# Microcontroleur.net
KiCad netlist of a schematic drawn in Altium Designer
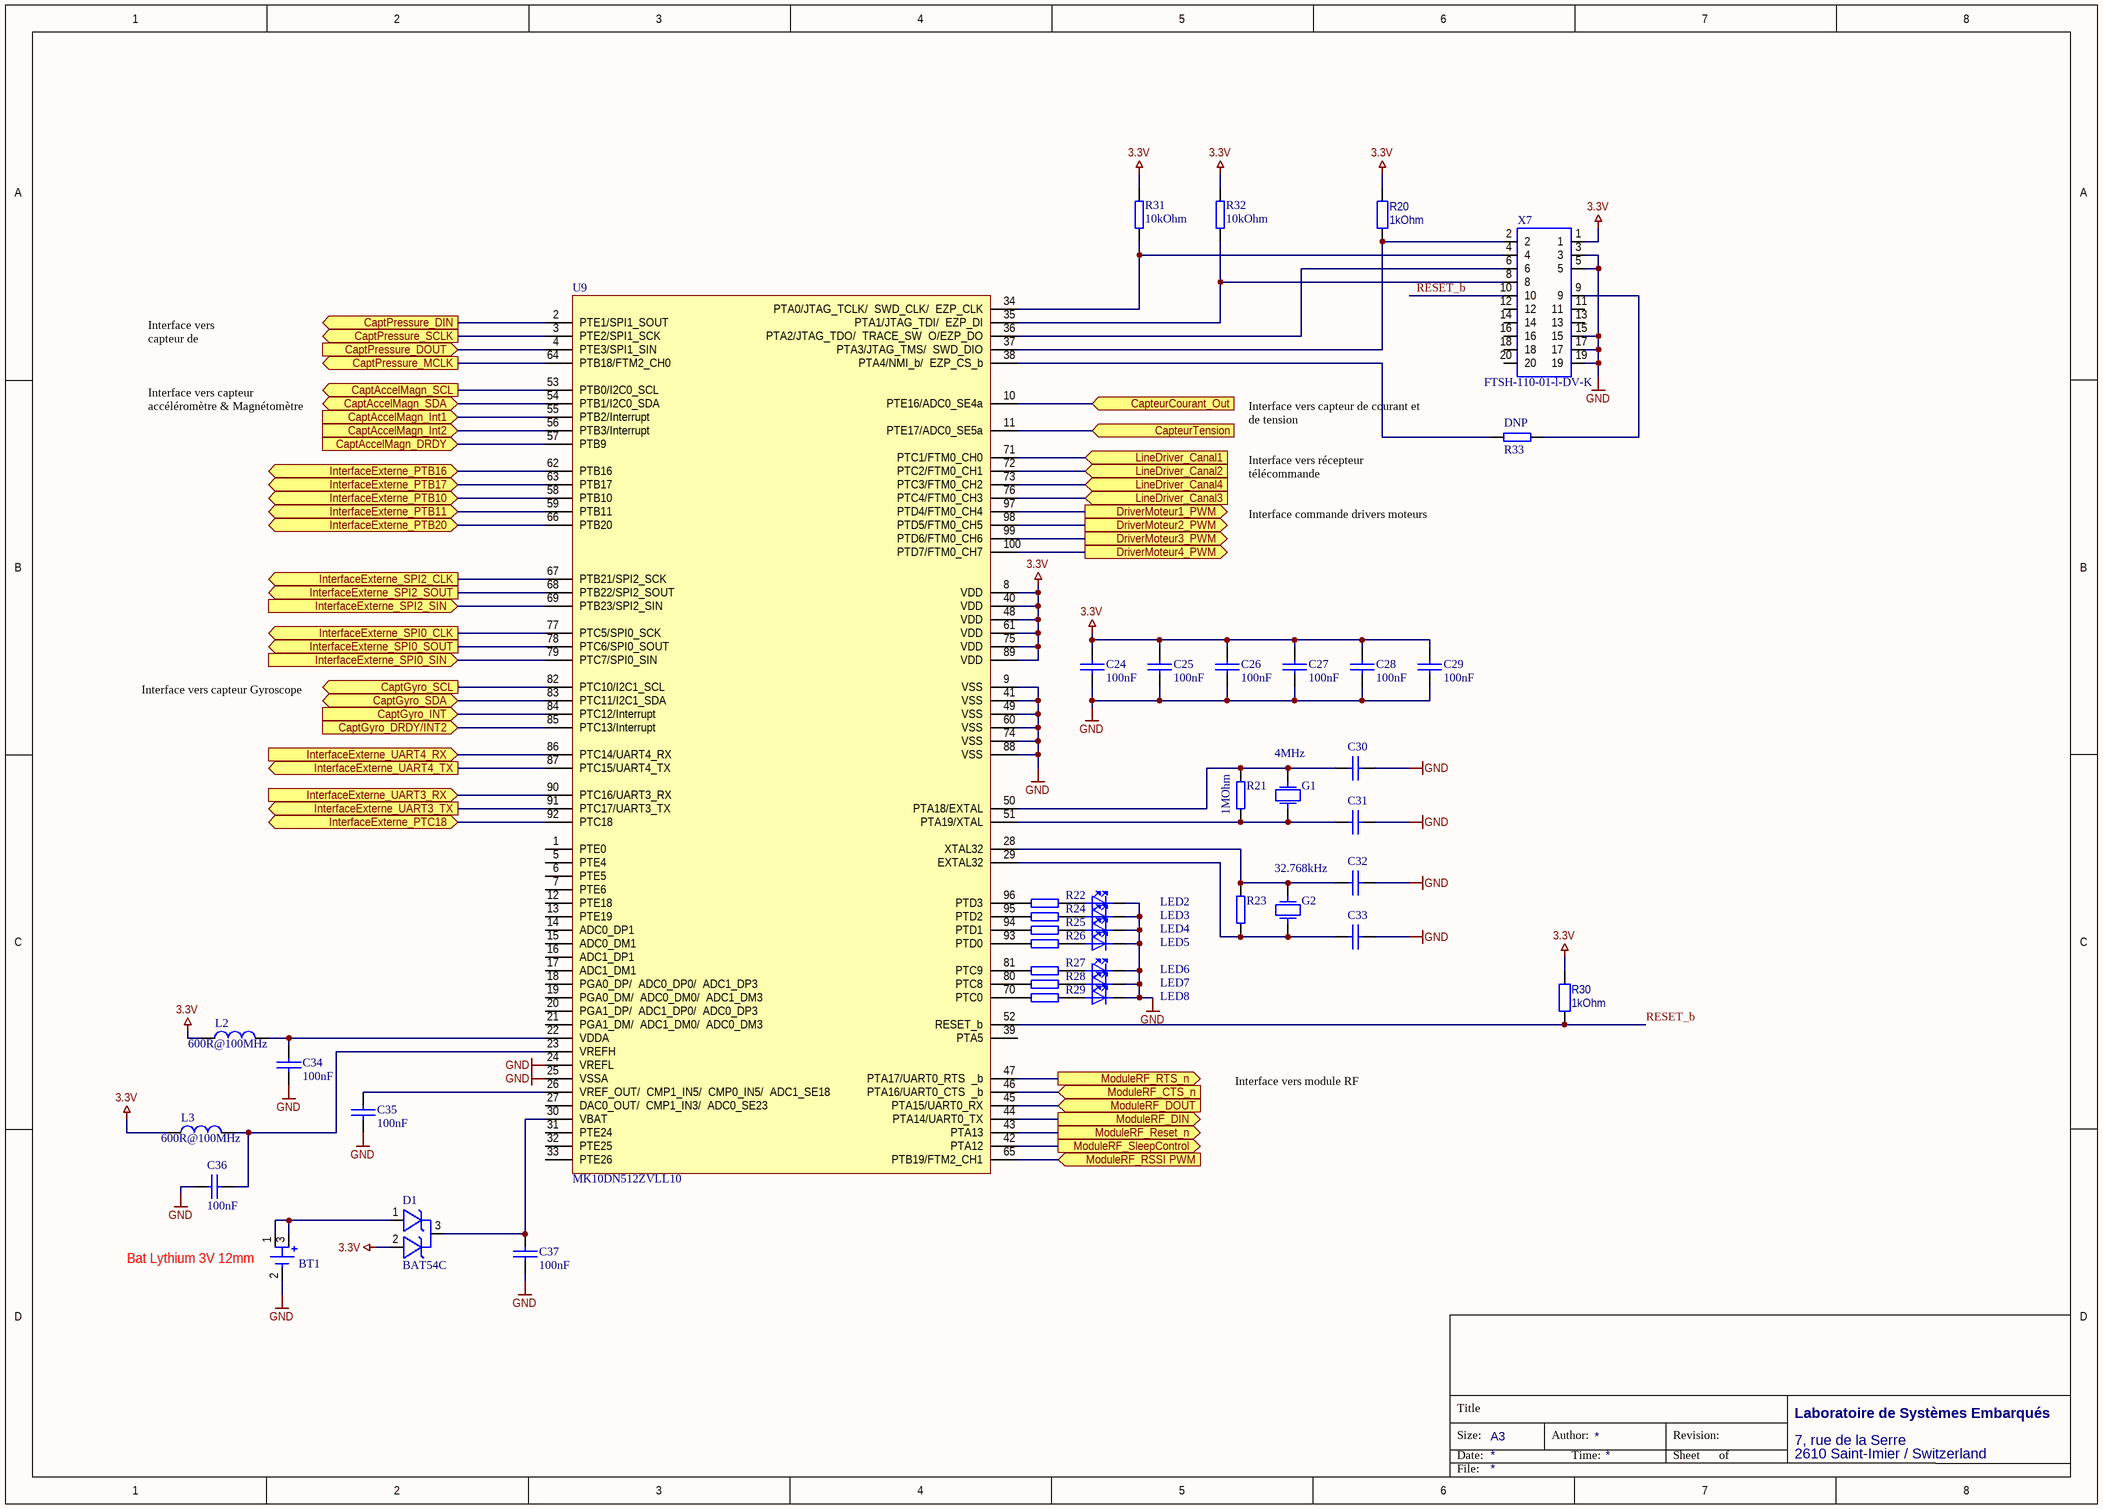
[diagram p0: Microcontroleur.SchDoc]

(export (version "E")
  (design (tool "Eeschema 10.0.6"))
  (components
    (comp (ref "BT1")
      (value "3000TR")
      (footprint "3000TR")
      (description "HOLDER BATTERY COIN 12MM DIA SMD")
      (fields (field (name "MANUFACTURER") "Keystone Electronics"))
      (libsource (lib "EISI") (part "BAT_1"))
    )
    (comp (ref "C24")
      (value "100nF")
      (footprint "060301")
      (description "CAPA")
      (fields (field (name "Comment") "GRM188R71E104KA01D"))
      (libsource (lib "General-Sch-205") (part "CAPA"))
    )
    (comp (ref "C25")
      (value "100nF")
      (footprint "060301")
      (description "CAPA")
      (fields (field (name "Comment") "GRM188R71E104KA01D"))
      (libsource (lib "General-Sch-205") (part "CAPA"))
    )
    (comp (ref "C26")
      (value "100nF")
      (footprint "060301")
      (description "CAPA")
      (fields (field (name "Comment") "GRM188R71E104KA01D"))
      (libsource (lib "General-Sch-205") (part "CAPA"))
    )
    (comp (ref "C27")
      (value "100nF")
      (footprint "060301")
      (description "CAPA")
      (fields (field (name "Comment") "GRM188R71E104KA01D"))
      (libsource (lib "General-Sch-205") (part "CAPA"))
    )
    (comp (ref "C28")
      (value "100nF")
      (footprint "060301")
      (description "CAPA")
      (fields (field (name "Comment") "GRM188R71E104KA01D"))
      (libsource (lib "General-Sch-205") (part "CAPA"))
    )
    (comp (ref "C29")
      (value "100nF")
      (footprint "060301")
      (description "CAPA")
      (fields (field (name "Comment") "GRM188R71E104KA01D"))
      (libsource (lib "General-Sch-205") (part "CAPA"))
    )
    (comp (ref "C30")
      (value "GQM2195C1H200JB01D")
      (footprint "060301")
      (description "CAPA")
      (libsource (lib "General-Sch-205") (part "CAPA"))
    )
    (comp (ref "C31")
      (value "GQM2195C1H200JB01D")
      (footprint "080501")
      (description "CAPA")
      (libsource (lib "General-Sch-205") (part "CAPA"))
    )
    (comp (ref "C32")
      (value "GRM21A5C2E120JW01D")
      (footprint "080501")
      (description "CAPA")
      (libsource (lib "General-Sch-205") (part "CAPA"))
    )
    (comp (ref "C33")
      (value "GRM21A5C2E120JW01D")
      (footprint "080501")
      (description "CAPA")
      (libsource (lib "General-Sch-205") (part "CAPA"))
    )
    (comp (ref "C34")
      (value "100nF")
      (footprint "060301")
      (description "CAPA")
      (fields (field (name "Comment") "GRM188R71E104KA01D"))
      (libsource (lib "General-Sch-205") (part "CAPA"))
    )
    (comp (ref "C35")
      (value "100nF")
      (footprint "060301")
      (description "CAPA")
      (fields (field (name "Comment") "GRM188R71E104KA01D"))
      (libsource (lib "General-Sch-205") (part "CAPA"))
    )
    (comp (ref "C36")
      (value "100nF")
      (footprint "060301")
      (description "CAPA")
      (fields (field (name "Comment") "GRM188R71E104KA01D"))
      (libsource (lib "General-Sch-205") (part "CAPA"))
    )
    (comp (ref "C37")
      (value "100nF")
      (footprint "060301")
      (description "CAPA")
      (fields (field (name "Comment") "GRM188R71E104KA01D"))
      (libsource (lib "General-Sch-205") (part "CAPA"))
    )
    (comp (ref "D1")
      (value "BAT54C")
      (footprint "SOT2301")
      (description "DIODE SCHTTKY CC 200MA 30V SOT23")
      (fields (field (name "MANUFACTURER") "Comchip Technology"))
      (libsource (lib "EISI") (part "BAT54C"))
    )
    (comp (ref "G1")
      (value "4MHz")
      (footprint "Crystal")
      (fields (field (name "Comment") "ECS-40-20-5PX-TR"))
      (libsource (lib "") (part "CRYSTAL_1"))
    )
    (comp (ref "G2")
      (value "32.768kHz")
      (footprint "Crystal2")
      (fields (field (name "Comment") "ECS-.327-12.5-38"))
      (libsource (lib "General-Sch-205") (part "CRYSTAL"))
    )
    (comp (ref "L2")
      (value "600R@100MHz")
      (footprint "080501")
      (description "FERRITE CHIP 600 OHM 200MA 0805")
      (fields (field (name "MANUFACTURER") "Murata Electronics") (field (name "Comment") "BLM21AG601SN1D"))
      (libsource (lib "EISI") (part "Ferrite Bead"))
    )
    (comp (ref "L3")
      (value "600R@100MHz")
      (footprint "080501")
      (description "FERRITE CHIP 600 OHM 200MA 0805")
      (fields (field (name "MANUFACTURER") "Murata Electronics") (field (name "Comment") "BLM21AG601SN1D"))
      (libsource (lib "EISI") (part "Ferrite Bead"))
    )
    (comp (ref "LED2")
      (value "LG L29K-G2J1-24-Z")
      (footprint "060301_led")
      (libsource (lib "Schlib1") (part "LED"))
    )
    (comp (ref "LED3")
      (value "LG L29K-G2J1-24-Z")
      (footprint "060301_led")
      (libsource (lib "Schlib1") (part "LED"))
    )
    (comp (ref "LED4")
      (value "LG L29K-G2J1-24-Z")
      (footprint "060301_led")
      (libsource (lib "Schlib1") (part "LED"))
    )
    (comp (ref "LED5")
      (value "LG L29K-G2J1-24-Z")
      (footprint "060301_led")
      (libsource (lib "Schlib1") (part "LED"))
    )
    (comp (ref "LED6")
      (value "LG L29K-G2J1-24-Z")
      (footprint "060301_led")
      (libsource (lib "Schlib1") (part "LED"))
    )
    (comp (ref "LED7")
      (value "LG L29K-G2J1-24-Z")
      (footprint "060301_led")
      (libsource (lib "Schlib1") (part "LED"))
    )
    (comp (ref "LED8")
      (value "LG L29K-G2J1-24-Z")
      (footprint "060301_led")
      (libsource (lib "Schlib1") (part "LED"))
    )
    (comp (ref "R20")
      (value "1kOhm")
      (footprint "060301")
      (description "RES 1.00K OHM 1/10W 1% 0603 SMD")
      (fields (field (name "MANUFACTURER") "Yageo") (field (name "Comment") "RC0603FR-071KL"))
      (libsource (lib "EISI") (part "RES"))
    )
    (comp (ref "R21")
      (value "1MOhm")
      (footprint "080501")
      (fields (field (name "Comment") "RMCF0805JT820R"))
      (libsource (lib "General-Sch-205") (part "RES"))
    )
    (comp (ref "R22")
      (value "RMCF0805JT820R")
      (footprint "080501")
      (libsource (lib "General-Sch-205") (part "RES"))
    )
    (comp (ref "R23")
      (value "ERJ-6GEYJ103V")
      (footprint "080501")
      (libsource (lib "General-Sch-205") (part "RES"))
    )
    (comp (ref "R24")
      (value "RMCF0805JT820R")
      (footprint "080501")
      (libsource (lib "General-Sch-205") (part "RES"))
    )
    (comp (ref "R25")
      (value "RMCF0805JT820R")
      (footprint "080501")
      (libsource (lib "General-Sch-205") (part "RES"))
    )
    (comp (ref "R26")
      (value "RMCF0805JT820R")
      (footprint "080501")
      (libsource (lib "General-Sch-205") (part "RES"))
    )
    (comp (ref "R27")
      (value "RMCF0805JT820R")
      (footprint "080501")
      (libsource (lib "General-Sch-205") (part "RES"))
    )
    (comp (ref "R28")
      (value "RMCF0805JT820R")
      (footprint "080501")
      (libsource (lib "General-Sch-205") (part "RES"))
    )
    (comp (ref "R29")
      (value "RMCF0805JT820R")
      (footprint "080501")
      (libsource (lib "General-Sch-205") (part "RES"))
    )
    (comp (ref "R30")
      (value "1kOhm")
      (footprint "060301")
      (description "RES 1.00K OHM 1/10W 1% 0603 SMD")
      (fields (field (name "MANUFACTURER") "Yageo") (field (name "Comment") "RC0603FR-071KL"))
      (libsource (lib "EISI") (part "RES"))
    )
    (comp (ref "R31")
      (value "10kOhm")
      (footprint "080501")
      (fields (field (name "Comment") "ERJ-6GEYJ103V"))
      (libsource (lib "General-Sch-205") (part "RES"))
    )
    (comp (ref "R32")
      (value "10kOhm")
      (footprint "080501")
      (fields (field (name "Comment") "ERJ-6GEYJ103V"))
      (libsource (lib "General-Sch-205") (part "RES"))
    )
    (comp (ref "R33")
      (value "DNP")
      (footprint "080501")
      (fields (field (name "Comment") "RMCF0805JT820R"))
      (libsource (lib "General-Sch-205") (part "RES"))
    )
    (comp (ref "U9")
      (value "MK10DN512ZVLL10")
      (footprint "QFP100-1")
      (libsource (lib "Schlib1") (part "MK10DN512ZVLL10"))
    )
    (comp (ref "X7")
      (value "FTSH-110-01-l-DV-K")
      (footprint "FTSH-110-01-X-DV-EJ")
      (description "CONN UNSHROUDED HDR 20POS .05\"")
      (fields (field (name "MANUFACTURER") "Samtec Inc"))
      (libsource (lib "EISI") (part "CON20_JTAG"))
    )
  )
  (nets
    (net (code "1") (name "/CaptAccelMagn_DRDY") (class "Default")
      (node (ref "U9") (pin "57") (pinfunction "PTB9_57") (pintype "passive"))
    )
    (net (code "2") (name "/CaptAccelMagn_Int1") (class "Default")
      (node (ref "U9") (pin "55") (pinfunction "PTB2/Interrupt_55") (pintype "passive"))
    )
    (net (code "3") (name "/CaptAccelMagn_Int2") (class "Default")
      (node (ref "U9") (pin "56") (pinfunction "PTB3/Interrupt_56") (pintype "passive"))
    )
    (net (code "4") (name "/CaptAccelMagn_SCL") (class "Default")
      (node (ref "U9") (pin "53") (pinfunction "PTB0/I2C0_SCL_53") (pintype "passive"))
    )
    (net (code "5") (name "/CaptAccelMagn_SDA") (class "Default")
      (node (ref "U9") (pin "54") (pinfunction "PTB1/I2C0_SDA_54") (pintype "passive"))
    )
    (net (code "6") (name "/CaptGyro_DRDY{slash}INT2") (class "Default")
      (node (ref "U9") (pin "85") (pinfunction "PTC13/Interrupt_85") (pintype "passive"))
    )
    (net (code "7") (name "/CaptGyro_INT") (class "Default")
      (node (ref "U9") (pin "84") (pinfunction "PTC12/Interrupt_84") (pintype "passive"))
    )
    (net (code "8") (name "/CaptGyro_SCL") (class "Default")
      (node (ref "U9") (pin "82") (pinfunction "PTC10/I2C1_SCL_82") (pintype "passive"))
    )
    (net (code "9") (name "/CaptGyro_SDA") (class "Default")
      (node (ref "U9") (pin "83") (pinfunction "PTC11/I2C1_SDA_83") (pintype "passive"))
    )
    (net (code "10") (name "/CaptPressure_DIN") (class "Default")
      (node (ref "U9") (pin "2") (pinfunction "PTE1/SPI1_SOUT_2") (pintype "passive"))
    )
    (net (code "11") (name "/CaptPressure_DOUT") (class "Default")
      (node (ref "U9") (pin "4") (pinfunction "PTE3/SPI1_SIN_4") (pintype "passive"))
    )
    (net (code "12") (name "/CaptPressure_MCLK") (class "Default")
      (node (ref "U9") (pin "64") (pinfunction "PTB18/FTM2_CH0_64") (pintype "passive"))
    )
    (net (code "13") (name "/CaptPressure_SCLK") (class "Default")
      (node (ref "U9") (pin "3") (pinfunction "PTE2/SPI1_SCK_3") (pintype "passive"))
    )
    (net (code "14") (name "/CapteurCourant_Out") (class "Default")
      (node (ref "U9") (pin "10") (pinfunction "PTE16/ADC0_SE4a_10") (pintype "passive"))
    )
    (net (code "15") (name "/CapteurTension") (class "Default")
      (node (ref "U9") (pin "11") (pinfunction "PTE17/ADC0_SE5a_11") (pintype "passive"))
    )
    (net (code "16") (name "/DriverMoteur1_PWM") (class "Default")
      (node (ref "U9") (pin "97") (pinfunction "PTD4/FTM0_CH4_97") (pintype "passive"))
    )
    (net (code "17") (name "/DriverMoteur2_PWM") (class "Default")
      (node (ref "U9") (pin "98") (pinfunction "PTD5/FTM0_CH5_98") (pintype "passive"))
    )
    (net (code "18") (name "/DriverMoteur3_PWM") (class "Default")
      (node (ref "U9") (pin "99") (pinfunction "PTD6/FTM0_CH6_99") (pintype "passive"))
    )
    (net (code "19") (name "/DriverMoteur4_PWM") (class "Default")
      (node (ref "U9") (pin "100") (pinfunction "PTD7/FTM0_CH7_100") (pintype "passive"))
    )
    (net (code "20") (name "/InterfaceExterne_PTB10") (class "Default")
      (node (ref "U9") (pin "58") (pinfunction "PTB10_58") (pintype "passive"))
    )
    (net (code "21") (name "/InterfaceExterne_PTB11") (class "Default")
      (node (ref "U9") (pin "59") (pinfunction "PTB11_59") (pintype "passive"))
    )
    (net (code "22") (name "/InterfaceExterne_PTB16") (class "Default")
      (node (ref "U9") (pin "62") (pinfunction "PTB16_62") (pintype "passive"))
    )
    (net (code "23") (name "/InterfaceExterne_PTB17") (class "Default")
      (node (ref "U9") (pin "63") (pinfunction "PTB17_63") (pintype "passive"))
    )
    (net (code "24") (name "/InterfaceExterne_PTB20") (class "Default")
      (node (ref "U9") (pin "66") (pinfunction "PTB20_66") (pintype "passive"))
    )
    (net (code "25") (name "/InterfaceExterne_PTC18") (class "Default")
      (node (ref "U9") (pin "92") (pinfunction "PTC18_92") (pintype "passive"))
    )
    (net (code "26") (name "/InterfaceExterne_SPI0_CLK") (class "Default")
      (node (ref "U9") (pin "77") (pinfunction "PTC5/SPI0_SCK_77") (pintype "passive"))
    )
    (net (code "27") (name "/InterfaceExterne_SPI0_SIN") (class "Default")
      (node (ref "U9") (pin "79") (pinfunction "PTC7/SPI0_SIN_79") (pintype "passive"))
    )
    (net (code "28") (name "/InterfaceExterne_SPI0_SOUT") (class "Default")
      (node (ref "U9") (pin "78") (pinfunction "PTC6/SPI0_SOUT_78") (pintype "passive"))
    )
    (net (code "29") (name "/InterfaceExterne_SPI2_CLK") (class "Default")
      (node (ref "U9") (pin "67") (pinfunction "PTB21/SPI2_SCK_67") (pintype "passive"))
    )
    (net (code "30") (name "/InterfaceExterne_SPI2_SIN") (class "Default")
      (node (ref "U9") (pin "69") (pinfunction "PTB23/SPI2_SIN_69") (pintype "passive"))
    )
    (net (code "31") (name "/InterfaceExterne_SPI2_SOUT") (class "Default")
      (node (ref "U9") (pin "68") (pinfunction "PTB22/SPI2_SOUT_68") (pintype "passive"))
    )
    (net (code "32") (name "/InterfaceExterne_UART3_RX") (class "Default")
      (node (ref "U9") (pin "90") (pinfunction "PTC16/UART3_RX_90") (pintype "passive"))
    )
    (net (code "33") (name "/InterfaceExterne_UART3_TX") (class "Default")
      (node (ref "U9") (pin "91") (pinfunction "PTC17/UART3_TX_91") (pintype "passive"))
    )
    (net (code "34") (name "/InterfaceExterne_UART4_RX") (class "Default")
      (node (ref "U9") (pin "86") (pinfunction "PTC14/UART4_RX_86") (pintype "passive"))
    )
    (net (code "35") (name "/InterfaceExterne_UART4_TX") (class "Default")
      (node (ref "U9") (pin "87") (pinfunction "PTC15/UART4_TX_87") (pintype "passive"))
    )
    (net (code "36") (name "/LineDriver_Canal1") (class "Default")
      (node (ref "U9") (pin "71") (pinfunction "PTC1/FTM0_CH0_71") (pintype "passive"))
    )
    (net (code "37") (name "/LineDriver_Canal2") (class "Default")
      (node (ref "U9") (pin "72") (pinfunction "PTC2/FTM0_CH1_72") (pintype "passive"))
    )
    (net (code "38") (name "/LineDriver_Canal3") (class "Default")
      (node (ref "U9") (pin "76") (pinfunction "PTC4/FTM0_CH3_76") (pintype "passive"))
    )
    (net (code "39") (name "/LineDriver_Canal4") (class "Default")
      (node (ref "U9") (pin "73") (pinfunction "PTC3/FTM0_CH2_73") (pintype "passive"))
    )
    (net (code "40") (name "/ModuleRF_CTS_n") (class "Default")
      (node (ref "U9") (pin "46") (pinfunction "PTA16/UART0_CTS___b_46") (pintype "passive"))
    )
    (net (code "41") (name "/ModuleRF_DIN") (class "Default")
      (node (ref "U9") (pin "44") (pinfunction "PTA14/UART0_TX_44") (pintype "passive"))
    )
    (net (code "42") (name "/ModuleRF_DOUT") (class "Default")
      (node (ref "U9") (pin "45") (pinfunction "PTA15/UART0_RX_45") (pintype "passive"))
    )
    (net (code "43") (name "/ModuleRF_RSSI PWM") (class "Default")
      (node (ref "U9") (pin "65") (pinfunction "PTB19/FTM2_CH1_65") (pintype "passive"))
    )
    (net (code "44") (name "/ModuleRF_RTS_n") (class "Default")
      (node (ref "U9") (pin "47") (pinfunction "PTA17/UART0_RTS___b_47") (pintype "passive"))
    )
    (net (code "45") (name "/ModuleRF_Reset_n") (class "Default")
      (node (ref "U9") (pin "43") (pinfunction "PTA13_43") (pintype "passive"))
    )
    (net (code "46") (name "/ModuleRF_SleepControl") (class "Default")
      (node (ref "U9") (pin "42") (pinfunction "PTA12_42") (pintype "passive"))
    )
    (net (code "47") (name "/RESET_b") (class "Default")
      (node (ref "R30") (pin "2") (pinfunction "2_2") (pintype "passive"))
      (node (ref "U9") (pin "52") (pinfunction "RESET_b_52") (pintype "passive"))
      (node (ref "X7") (pin "10") (pinfunction "10_10") (pintype "passive"))
    )
    (net (code "48") (name "3.3V") (class "Default")
      (node (ref "C24") (pin "1") (pintype "passive"))
      (node (ref "C25") (pin "1") (pintype "passive"))
      (node (ref "C26") (pin "1") (pintype "passive"))
      (node (ref "C27") (pin "1") (pintype "passive"))
      (node (ref "C28") (pin "1") (pintype "passive"))
      (node (ref "C29") (pin "1") (pintype "passive"))
      (node (ref "D1") (pin "2") (pinfunction "C2_2") (pintype "passive"))
      (node (ref "L2") (pin "1") (pinfunction "1_1") (pintype "passive"))
      (node (ref "L3") (pin "1") (pinfunction "1_1") (pintype "passive"))
      (node (ref "R20") (pin "1") (pinfunction "1_1") (pintype "passive"))
      (node (ref "R30") (pin "1") (pinfunction "1_1") (pintype "passive"))
      (node (ref "R31") (pin "2") (pintype "passive"))
      (node (ref "R32") (pin "2") (pintype "passive"))
      (node (ref "U9") (pin "40") (pinfunction "VDD_40") (pintype "passive"))
      (node (ref "U9") (pin "48") (pinfunction "VDD_48") (pintype "passive"))
      (node (ref "U9") (pin "61") (pinfunction "VDD_61") (pintype "passive"))
      (node (ref "U9") (pin "75") (pinfunction "VDD_75") (pintype "passive"))
      (node (ref "U9") (pin "8") (pinfunction "VDD_8") (pintype "passive"))
      (node (ref "U9") (pin "89") (pinfunction "VDD_89") (pintype "passive"))
      (node (ref "X7") (pin "1") (pinfunction "1_1") (pintype "passive"))
    )
    (net (code "49") (name "GND") (class "Default")
      (node (ref "BT1") (pin "2") (pinfunction "C_2") (pintype "passive"))
      (node (ref "C24") (pin "2") (pintype "passive"))
      (node (ref "C25") (pin "2") (pintype "passive"))
      (node (ref "C26") (pin "2") (pintype "passive"))
      (node (ref "C27") (pin "2") (pintype "passive"))
      (node (ref "C28") (pin "2") (pintype "passive"))
      (node (ref "C29") (pin "2") (pintype "passive"))
      (node (ref "C30") (pin "2") (pintype "passive"))
      (node (ref "C31") (pin "2") (pintype "passive"))
      (node (ref "C32") (pin "2") (pintype "passive"))
      (node (ref "C33") (pin "2") (pintype "passive"))
      (node (ref "C34") (pin "2") (pintype "passive"))
      (node (ref "C35") (pin "1") (pintype "passive"))
      (node (ref "C36") (pin "1") (pintype "passive"))
      (node (ref "C37") (pin "1") (pintype "passive"))
      (node (ref "LED2") (pin "2") (pinfunction "CATHODE_2") (pintype "passive"))
      (node (ref "LED3") (pin "2") (pinfunction "CATHODE_2") (pintype "passive"))
      (node (ref "LED4") (pin "2") (pinfunction "CATHODE_2") (pintype "passive"))
      (node (ref "LED5") (pin "2") (pinfunction "CATHODE_2") (pintype "passive"))
      (node (ref "LED6") (pin "2") (pinfunction "CATHODE_2") (pintype "passive"))
      (node (ref "LED7") (pin "2") (pinfunction "CATHODE_2") (pintype "passive"))
      (node (ref "LED8") (pin "2") (pinfunction "CATHODE_2") (pintype "passive"))
      (node (ref "U9") (pin "24") (pinfunction "VREFL_24") (pintype "passive"))
      (node (ref "U9") (pin "25") (pinfunction "VSSA_25") (pintype "passive"))
      (node (ref "U9") (pin "41") (pinfunction "VSS_41") (pintype "passive"))
      (node (ref "U9") (pin "49") (pinfunction "VSS_49") (pintype "passive"))
      (node (ref "U9") (pin "60") (pinfunction "VSS_60") (pintype "passive"))
      (node (ref "U9") (pin "74") (pinfunction "VSS_74") (pintype "passive"))
      (node (ref "U9") (pin "88") (pinfunction "VSS_88") (pintype "passive"))
      (node (ref "U9") (pin "9") (pinfunction "VSS_9") (pintype "passive"))
      (node (ref "X7") (pin "15") (pinfunction "15_15") (pintype "passive"))
      (node (ref "X7") (pin "17") (pinfunction "17_17") (pintype "passive"))
      (node (ref "X7") (pin "19") (pinfunction "19_19") (pintype "passive"))
      (node (ref "X7") (pin "3") (pinfunction "3_3") (pintype "passive"))
      (node (ref "X7") (pin "5") (pinfunction "5_5") (pintype "passive"))
    )
    (net (code "50") (name "Net-(BT1-A1)") (class "Default")
      (node (ref "BT1") (pin "1") (pinfunction "A1_1") (pintype "passive"))
      (node (ref "BT1") (pin "3") (pinfunction "A2_3") (pintype "passive"))
      (node (ref "D1") (pin "1") (pinfunction "C1_1") (pintype "passive"))
    )
    (net (code "51") (name "Net-(D1-Anode)") (class "Default")
      (node (ref "C37") (pin "2") (pintype "passive"))
      (node (ref "D1") (pin "3") (pinfunction "Anode_3") (pintype "passive"))
      (node (ref "U9") (pin "30") (pinfunction "VBAT_30") (pintype "passive"))
    )
    (net (code "52") (name "Net-(LED2-ANODE)") (class "Default")
      (node (ref "LED2") (pin "1") (pinfunction "ANODE_1") (pintype "passive"))
      (node (ref "R24") (pin "2") (pintype "passive"))
    )
    (net (code "53") (name "Net-(LED3-ANODE)") (class "Default")
      (node (ref "LED3") (pin "1") (pinfunction "ANODE_1") (pintype "passive"))
      (node (ref "R22") (pin "2") (pintype "passive"))
    )
    (net (code "54") (name "Net-(LED4-ANODE)") (class "Default")
      (node (ref "LED4") (pin "1") (pinfunction "ANODE_1") (pintype "passive"))
      (node (ref "R25") (pin "2") (pintype "passive"))
    )
    (net (code "55") (name "Net-(LED5-ANODE)") (class "Default")
      (node (ref "LED5") (pin "1") (pinfunction "ANODE_1") (pintype "passive"))
      (node (ref "R26") (pin "2") (pintype "passive"))
    )
    (net (code "56") (name "Net-(LED6-ANODE)") (class "Default")
      (node (ref "LED6") (pin "1") (pinfunction "ANODE_1") (pintype "passive"))
      (node (ref "R27") (pin "2") (pintype "passive"))
    )
    (net (code "57") (name "Net-(LED7-ANODE)") (class "Default")
      (node (ref "LED7") (pin "1") (pinfunction "ANODE_1") (pintype "passive"))
      (node (ref "R28") (pin "2") (pintype "passive"))
    )
    (net (code "58") (name "Net-(LED8-ANODE)") (class "Default")
      (node (ref "LED8") (pin "1") (pinfunction "ANODE_1") (pintype "passive"))
      (node (ref "R29") (pin "2") (pintype "passive"))
    )
    (net (code "59") (name "Net-(R33-Pad1)") (class "Default")
      (node (ref "R33") (pin "1") (pintype "passive"))
      (node (ref "X7") (pin "9") (pinfunction "9_9") (pintype "passive"))
    )
    (net (code "60") (name "Net-(U9-EXTAL32)") (class "Default")
      (node (ref "C33") (pin "1") (pintype "passive"))
      (node (ref "G2") (pin "1") (pintype "passive"))
      (node (ref "R23") (pin "1") (pintype "passive"))
      (node (ref "U9") (pin "29") (pinfunction "EXTAL32_29") (pintype "passive"))
    )
    (net (code "61") (name "Net-(U9-PTA0{slash}JTAG_TCLK{slash}__SWD_CLK{slash}__EZP_CLK)") (class "Default")
      (node (ref "R31") (pin "1") (pintype "passive"))
      (node (ref "U9") (pin "34") (pinfunction "PTA0/JTAG_TCLK/__SWD_CLK/__EZP_CLK_34") (pintype "passive"))
      (node (ref "X7") (pin "4") (pinfunction "4_4") (pintype "passive"))
    )
    (net (code "62") (name "Net-(U9-PTA1{slash}JTAG_TDI{slash}__EZP_DI)") (class "Default")
      (node (ref "R32") (pin "1") (pintype "passive"))
      (node (ref "U9") (pin "35") (pinfunction "PTA1/JTAG_TDI/__EZP_DI_35") (pintype "passive"))
      (node (ref "X7") (pin "8") (pinfunction "8_8") (pintype "passive"))
    )
    (net (code "63") (name "Net-(U9-PTA2{slash}JTAG_TDO{slash}__TRACE_SW__O{slash}EZP_DO)") (class "Default")
      (node (ref "U9") (pin "36") (pinfunction "PTA2/JTAG_TDO/__TRACE_SW__O/EZP_DO_36") (pintype "passive"))
      (node (ref "X7") (pin "6") (pinfunction "6_6") (pintype "passive"))
    )
    (net (code "64") (name "Net-(U9-PTA3{slash}JTAG_TMS{slash}__SWD_DIO)") (class "Default")
      (node (ref "R20") (pin "2") (pinfunction "2_2") (pintype "passive"))
      (node (ref "U9") (pin "37") (pinfunction "PTA3/JTAG_TMS/__SWD_DIO_37") (pintype "passive"))
      (node (ref "X7") (pin "2") (pinfunction "2_2") (pintype "passive"))
    )
    (net (code "65") (name "Net-(U9-PTA4{slash}NMI_b{slash}__EZP_CS_b)") (class "Default")
      (node (ref "R33") (pin "2") (pintype "passive"))
      (node (ref "U9") (pin "38") (pinfunction "PTA4/NMI_b/__EZP_CS_b_38") (pintype "passive"))
    )
    (net (code "66") (name "Net-(U9-PTA18{slash}EXTAL)") (class "Default")
      (node (ref "C30") (pin "1") (pintype "passive"))
      (node (ref "G1") (pin "1") (pintype "passive"))
      (node (ref "R21") (pin "2") (pintype "passive"))
      (node (ref "U9") (pin "50") (pinfunction "PTA18/EXTAL_50") (pintype "passive"))
    )
    (net (code "67") (name "Net-(U9-PTA19{slash}XTAL)") (class "Default")
      (node (ref "C31") (pin "1") (pintype "passive"))
      (node (ref "G1") (pin "2") (pinfunction "2_2") (pintype "passive"))
      (node (ref "R21") (pin "1") (pintype "passive"))
      (node (ref "U9") (pin "51") (pinfunction "PTA19/XTAL_51") (pintype "passive"))
    )
    (net (code "68") (name "Net-(U9-PTC0)") (class "Default")
      (node (ref "R29") (pin "1") (pintype "passive"))
      (node (ref "U9") (pin "70") (pinfunction "PTC0_70") (pintype "passive"))
    )
    (net (code "69") (name "Net-(U9-PTC8)") (class "Default")
      (node (ref "R28") (pin "1") (pintype "passive"))
      (node (ref "U9") (pin "80") (pinfunction "PTC8_80") (pintype "passive"))
    )
    (net (code "70") (name "Net-(U9-PTC9)") (class "Default")
      (node (ref "R27") (pin "1") (pintype "passive"))
      (node (ref "U9") (pin "81") (pinfunction "PTC9_81") (pintype "passive"))
    )
    (net (code "71") (name "Net-(U9-PTD0)") (class "Default")
      (node (ref "R26") (pin "1") (pintype "passive"))
      (node (ref "U9") (pin "93") (pinfunction "PTD0_93") (pintype "passive"))
    )
    (net (code "72") (name "Net-(U9-PTD1)") (class "Default")
      (node (ref "R25") (pin "1") (pintype "passive"))
      (node (ref "U9") (pin "94") (pinfunction "PTD1_94") (pintype "passive"))
    )
    (net (code "73") (name "Net-(U9-PTD2)") (class "Default")
      (node (ref "R24") (pin "1") (pintype "passive"))
      (node (ref "U9") (pin "95") (pinfunction "PTD2_95") (pintype "passive"))
    )
    (net (code "74") (name "Net-(U9-PTD3)") (class "Default")
      (node (ref "R22") (pin "1") (pintype "passive"))
      (node (ref "U9") (pin "96") (pinfunction "PTD3_96") (pintype "passive"))
    )
    (net (code "75") (name "Net-(U9-VDDA)") (class "Default")
      (node (ref "C34") (pin "1") (pintype "passive"))
      (node (ref "L2") (pin "2") (pinfunction "2_2") (pintype "passive"))
      (node (ref "U9") (pin "22") (pinfunction "VDDA_22") (pintype "passive"))
    )
    (net (code "76") (name "Net-(U9-VREFH)") (class "Default")
      (node (ref "C36") (pin "2") (pintype "passive"))
      (node (ref "L3") (pin "2") (pinfunction "2_2") (pintype "passive"))
      (node (ref "U9") (pin "23") (pinfunction "VREFH_23") (pintype "passive"))
    )
    (net (code "77") (name "Net-(U9-VREF_OUT{slash}__CMP1_IN5{slash}__CMP0_IN5{slash}__ADC1_SE18)") (class "Default")
      (node (ref "C35") (pin "2") (pintype "passive"))
      (node (ref "U9") (pin "26") (pinfunction "VREF_OUT/__CMP1_IN5/__CMP0_IN5/__ADC1_SE18_26") (pintype "passive"))
    )
    (net (code "78") (name "Net-(U9-XTAL32)") (class "Default")
      (node (ref "C32") (pin "1") (pintype "passive"))
      (node (ref "G2") (pin "2") (pintype "passive"))
      (node (ref "R23") (pin "2") (pintype "passive"))
      (node (ref "U9") (pin "28") (pinfunction "XTAL32_28") (pintype "passive"))
    )
    (net (code "79") (name "unconnected-(U9-ADC0_DM1-Pad15)") (class "Default")
      (node (ref "U9") (pin "15") (pinfunction "ADC0_DM1_15") (pintype "passive"))
    )
    (net (code "80") (name "unconnected-(U9-ADC0_DP1-Pad14)") (class "Default")
      (node (ref "U9") (pin "14") (pinfunction "ADC0_DP1_14") (pintype "passive"))
    )
    (net (code "81") (name "unconnected-(U9-ADC1_DM1-Pad17)") (class "Default")
      (node (ref "U9") (pin "17") (pinfunction "ADC1_DM1_17") (pintype "passive"))
    )
    (net (code "82") (name "unconnected-(U9-ADC1_DP1-Pad16)") (class "Default")
      (node (ref "U9") (pin "16") (pinfunction "ADC1_DP1_16") (pintype "passive"))
    )
    (net (code "83") (name "unconnected-(U9-DAC0_OUT{slash}__CMP1_IN3{slash}__ADC0_SE23-Pad27)") (class "Default")
      (node (ref "U9") (pin "27") (pinfunction "DAC0_OUT/__CMP1_IN3/__ADC0_SE23_27") (pintype "passive"))
    )
    (net (code "84") (name "unconnected-(U9-PGA0_DM{slash}__ADC0_DM0{slash}__ADC1_DM3-Pad19)") (class "Default")
      (node (ref "U9") (pin "19") (pinfunction "PGA0_DM/__ADC0_DM0/__ADC1_DM3_19") (pintype "passive"))
    )
    (net (code "85") (name "unconnected-(U9-PGA0_DP{slash}__ADC0_DP0{slash}__ADC1_DP3-Pad18)") (class "Default")
      (node (ref "U9") (pin "18") (pinfunction "PGA0_DP/__ADC0_DP0/__ADC1_DP3_18") (pintype "passive"))
    )
    (net (code "86") (name "unconnected-(U9-PGA1_DM{slash}__ADC1_DM0{slash}__ADC0_DM3-Pad21)") (class "Default")
      (node (ref "U9") (pin "21") (pinfunction "PGA1_DM/__ADC1_DM0/__ADC0_DM3_21") (pintype "passive"))
    )
    (net (code "87") (name "unconnected-(U9-PGA1_DP{slash}__ADC1_DP0{slash}__ADC0_DP3-Pad20)") (class "Default")
      (node (ref "U9") (pin "20") (pinfunction "PGA1_DP/__ADC1_DP0/__ADC0_DP3_20") (pintype "passive"))
    )
    (net (code "88") (name "unconnected-(U9-PTA5-Pad39)") (class "Default")
      (node (ref "U9") (pin "39") (pinfunction "PTA5_39") (pintype "passive"))
    )
    (net (code "89") (name "unconnected-(U9-PTE0-Pad1)") (class "Default")
      (node (ref "U9") (pin "1") (pinfunction "PTE0_1") (pintype "passive"))
    )
    (net (code "90") (name "unconnected-(U9-PTE4-Pad5)") (class "Default")
      (node (ref "U9") (pin "5") (pinfunction "PTE4_5") (pintype "passive"))
    )
    (net (code "91") (name "unconnected-(U9-PTE5-Pad6)") (class "Default")
      (node (ref "U9") (pin "6") (pinfunction "PTE5_6") (pintype "passive"))
    )
    (net (code "92") (name "unconnected-(U9-PTE6-Pad7)") (class "Default")
      (node (ref "U9") (pin "7") (pinfunction "PTE6_7") (pintype "passive"))
    )
    (net (code "93") (name "unconnected-(U9-PTE18-Pad12)") (class "Default")
      (node (ref "U9") (pin "12") (pinfunction "PTE18_12") (pintype "passive"))
    )
    (net (code "94") (name "unconnected-(U9-PTE19-Pad13)") (class "Default")
      (node (ref "U9") (pin "13") (pinfunction "PTE19_13") (pintype "passive"))
    )
    (net (code "95") (name "unconnected-(U9-PTE24-Pad31)") (class "Default")
      (node (ref "U9") (pin "31") (pinfunction "PTE24_31") (pintype "passive"))
    )
    (net (code "96") (name "unconnected-(U9-PTE25-Pad32)") (class "Default")
      (node (ref "U9") (pin "32") (pinfunction "PTE25_32") (pintype "passive"))
    )
    (net (code "97") (name "unconnected-(U9-PTE26-Pad33)") (class "Default")
      (node (ref "U9") (pin "33") (pinfunction "PTE26_33") (pintype "passive"))
    )
    (net (code "98") (name "unconnected-(X7-Pad11)") (class "Default")
      (node (ref "X7") (pin "11") (pinfunction "11_11") (pintype "passive"))
    )
    (net (code "99") (name "unconnected-(X7-Pad12)") (class "Default")
      (node (ref "X7") (pin "12") (pinfunction "12_12") (pintype "passive"))
    )
    (net (code "100") (name "unconnected-(X7-Pad13)") (class "Default")
      (node (ref "X7") (pin "13") (pinfunction "13_13") (pintype "passive"))
    )
    (net (code "101") (name "unconnected-(X7-Pad14)") (class "Default")
      (node (ref "X7") (pin "14") (pinfunction "14_14") (pintype "passive"))
    )
    (net (code "102") (name "unconnected-(X7-Pad16)") (class "Default")
      (node (ref "X7") (pin "16") (pinfunction "16_16") (pintype "passive"))
    )
    (net (code "103") (name "unconnected-(X7-Pad18)") (class "Default")
      (node (ref "X7") (pin "18") (pinfunction "18_18") (pintype "passive"))
    )
    (net (code "104") (name "unconnected-(X7-Pad20)") (class "Default")
      (node (ref "X7") (pin "20") (pinfunction "20_20") (pintype "passive"))
    )
  )
)
